# Adafruit_Feather_328P.net
KiCad netlist of a schematic drawn in EAGLE
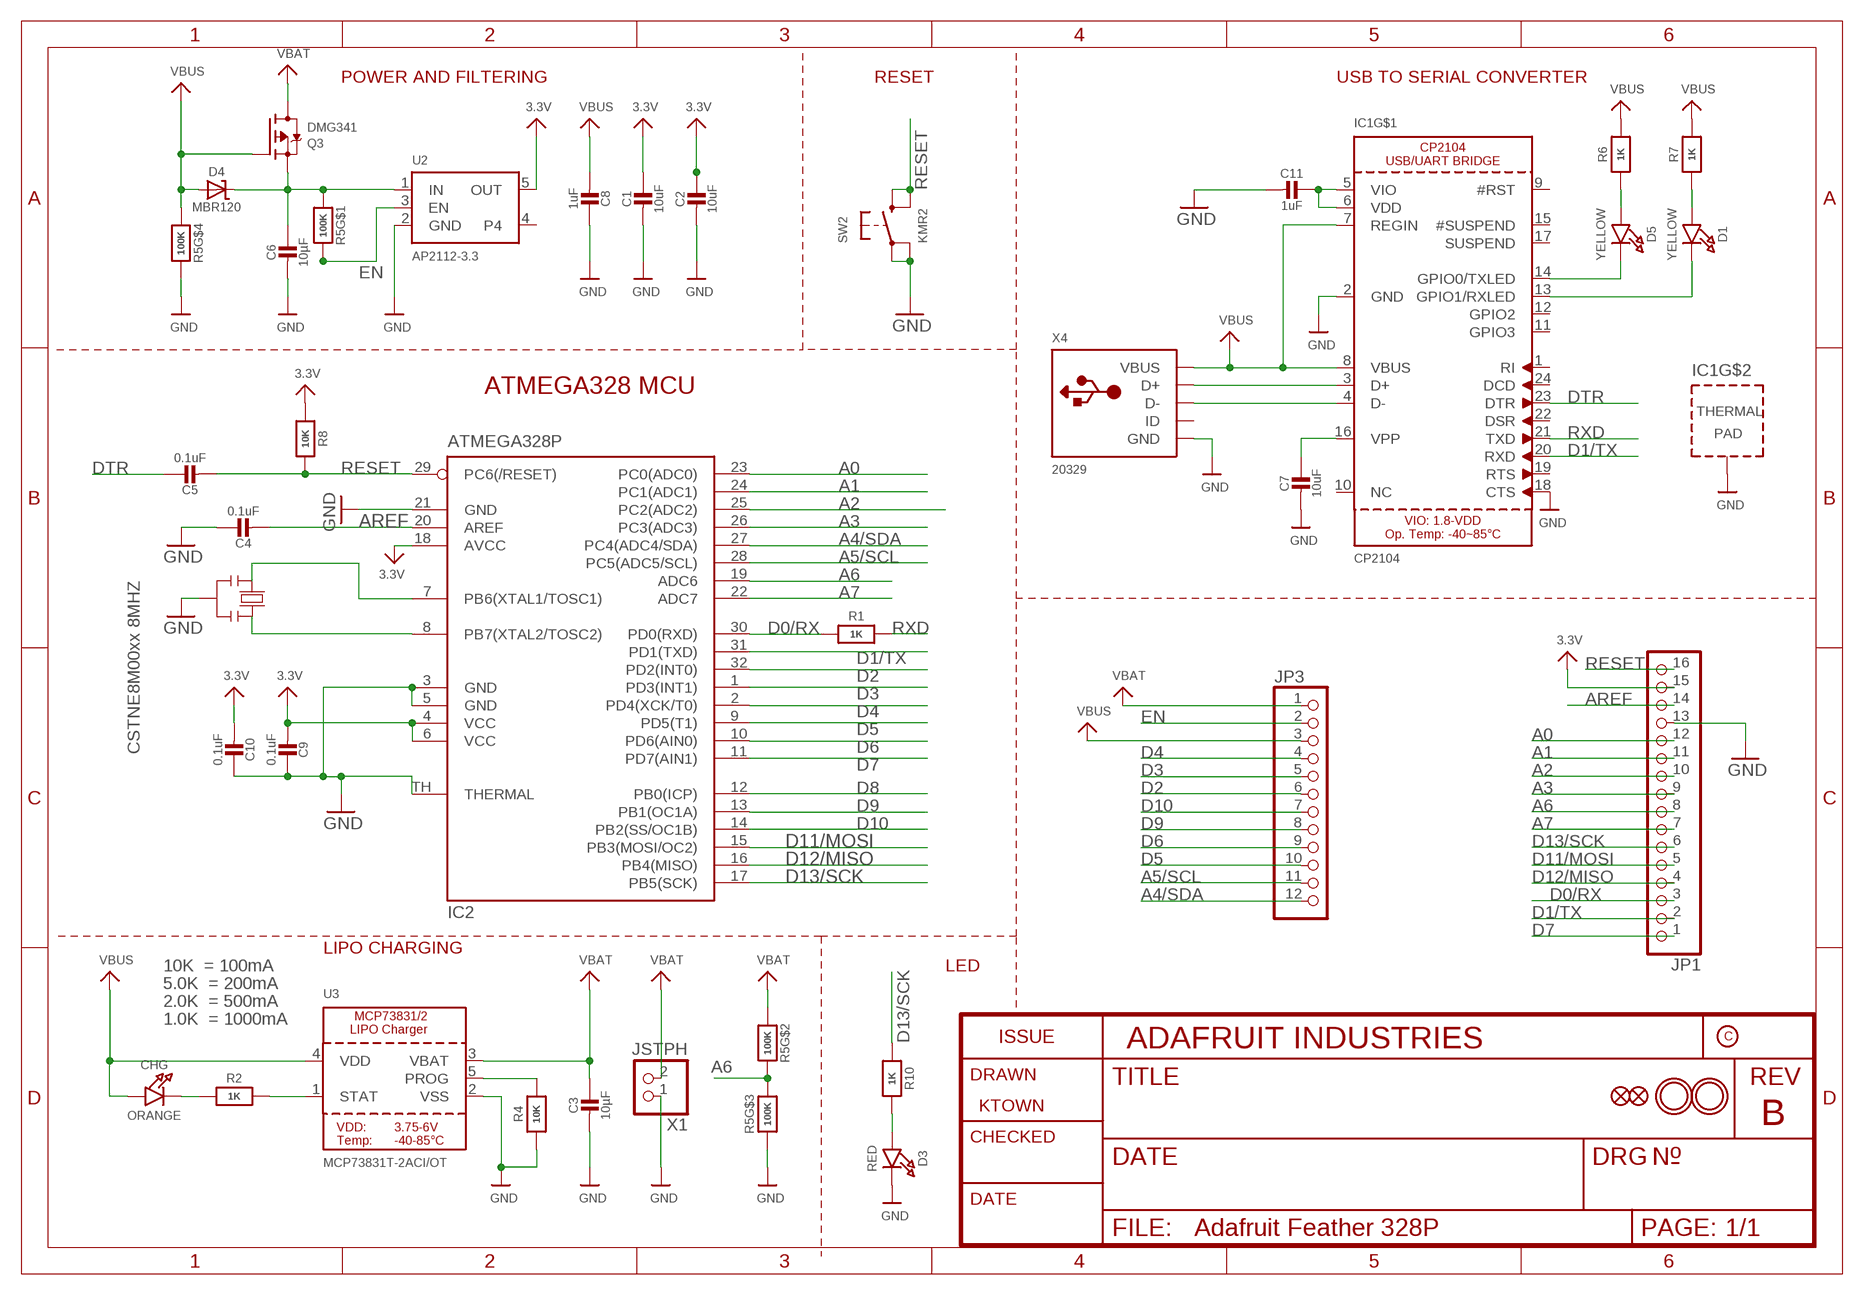
[diagram p0: schematic, sheet 1]

(export (version "E")
  (design (tool "Eeschema 10.0.6"))
  (components
    (comp (ref "C1")
      (value "10uF")
      (footprint "eagle-import:0805-NO")
      (libsource (lib "eagle-import") (part "CAP_CERAMIC0805-NOOUTLINE"))
    )
    (comp (ref "C2")
      (value "10uF")
      (footprint "eagle-import:0805-NO")
      (libsource (lib "eagle-import") (part "CAP_CERAMIC0805-NOOUTLINE"))
    )
    (comp (ref "C3")
      (value "10µF")
      (footprint "eagle-import:0805-NO")
      (libsource (lib "eagle-import") (part "CAP_CERAMIC0805-NOOUTLINE"))
    )
    (comp (ref "C4")
      (value "0.1uF")
      (footprint "eagle-import:0603-NO")
      (libsource (lib "eagle-import") (part "CAP_CERAMIC0603_NO"))
    )
    (comp (ref "C5")
      (value "0.1uF")
      (footprint "eagle-import:0603-NO")
      (libsource (lib "eagle-import") (part "CAP_CERAMIC0603_NO"))
    )
    (comp (ref "C6")
      (value "10µF")
      (footprint "eagle-import:0805-NO")
      (libsource (lib "eagle-import") (part "CAP_CERAMIC0805-NOOUTLINE"))
    )
    (comp (ref "C7")
      (value "10uF")
      (footprint "eagle-import:_0805MP")
      (libsource (lib "eagle-import") (part "CAP_CERAMIC_0805MP"))
    )
    (comp (ref "C8")
      (value "1uF")
      (footprint "eagle-import:0603-NO")
      (libsource (lib "eagle-import") (part "CAP_CERAMIC0603_NO"))
    )
    (comp (ref "C9")
      (value "0.1uF")
      (footprint "eagle-import:0603-NO")
      (libsource (lib "eagle-import") (part "CAP_CERAMIC0603_NO"))
    )
    (comp (ref "C10")
      (value "0.1uF")
      (footprint "eagle-import:0603-NO")
      (libsource (lib "eagle-import") (part "CAP_CERAMIC0603_NO"))
    )
    (comp (ref "C11")
      (value "1uF")
      (footprint "eagle-import:0603-NO")
      (libsource (lib "eagle-import") (part "CAP_CERAMIC0603_NO"))
    )
    (comp (ref "CHG")
      (value "ORANGE")
      (footprint "eagle-import:CHIPLED_0805_NOOUTLINE")
      (libsource (lib "eagle-import") (part "LED0805_NOOUTLINE"))
    )
    (comp (ref "D1")
      (value "YELLOW")
      (footprint "eagle-import:CHIPLED_0805_NOOUTLINE")
      (libsource (lib "eagle-import") (part "LED0805_NOOUTLINE"))
    )
    (comp (ref "D3")
      (value "RED")
      (footprint "eagle-import:CHIPLED_0805_NOOUTLINE")
      (libsource (lib "eagle-import") (part "LED0805_NOOUTLINE"))
    )
    (comp (ref "D4")
      (value "MBR120")
      (footprint "eagle-import:SOD-123")
      (libsource (lib "eagle-import") (part "DIODE-SCHOTTKYSOD-123"))
    )
    (comp (ref "D5")
      (value "YELLOW")
      (footprint "eagle-import:CHIPLED_0805_NOOUTLINE")
      (libsource (lib "eagle-import") (part "LED0805_NOOUTLINE"))
    )
    (comp (ref "IC1")
      (value "CP2104")
      (footprint "eagle-import:QFN24_4MM_SMSC")
      (libsource (lib "eagle-import") (part "CP2104"))
    )
    (comp (ref "IC2")
      (value "ATMEGA328P")
      (footprint "eagle-import:MLF32-TH")
      (fields (field (name "MPN") "ATMEGA88PA-MU"))
      (libsource (lib "eagle-import") (part "MEGA8-MI"))
    )
    (comp (ref "JP1")
      (value "HEADER-1X16ROUND")
      (footprint "eagle-import:1X16_ROUND")
      (libsource (lib "eagle-import") (part "HEADER-1X16ROUND"))
    )
    (comp (ref "JP3")
      (value "HEADER-1X12")
      (footprint "eagle-import:1X12_ROUND")
      (libsource (lib "eagle-import") (part "HEADER-1X12"))
    )
    (comp (ref "Q3")
      (value "DMG341")
      (footprint "eagle-import:SOT23-R")
      (libsource (lib "eagle-import") (part "MOSFET-P"))
    )
    (comp (ref "R1")
      (value "1K")
      (footprint "eagle-import:_0603MP")
      (libsource (lib "eagle-import") (part "RESISTOR_0603MP"))
    )
    (comp (ref "R2")
      (value "1K")
      (footprint "eagle-import:0603-NO")
      (libsource (lib "eagle-import") (part "RESISTOR_0603_NOOUT"))
    )
    (comp (ref "R4")
      (value "10K")
      (footprint "eagle-import:0603-NO")
      (libsource (lib "eagle-import") (part "RESISTOR_0603_NOOUT"))
    )
    (comp (ref "R5")
      (value "100K")
      (footprint "eagle-import:RESPACK_4X0603")
      (libsource (lib "eagle-import") (part "RESISTOR_4PACK"))
    )
    (comp (ref "R6")
      (value "1K")
      (footprint "eagle-import:0603-NO")
      (libsource (lib "eagle-import") (part "RESISTOR_0603_NOOUT"))
    )
    (comp (ref "R7")
      (value "1K")
      (footprint "eagle-import:0603-NO")
      (libsource (lib "eagle-import") (part "RESISTOR_0603_NOOUT"))
    )
    (comp (ref "R8")
      (value "10K")
      (footprint "eagle-import:0603-NO")
      (libsource (lib "eagle-import") (part "RESISTOR_0603_NOOUT"))
    )
    (comp (ref "R10")
      (value "1K")
      (footprint "eagle-import:0603-NO")
      (libsource (lib "eagle-import") (part "RESISTOR_0603_NOOUT"))
    )
    (comp (ref "SW2")
      (value "KMR2")
      (footprint "eagle-import:BTN_KMR2_4.6X2.8")
      (libsource (lib "eagle-import") (part "SWITCH_TACT_SMT4.6X2.8"))
    )
    (comp (ref "U$31")
      (value "MOUNTINGHOLE2.5")
      (footprint "eagle-import:MOUNTINGHOLE_2.5_PLATED")
      (libsource (lib "eagle-import") (part "MOUNTINGHOLE2.5"))
    )
    (comp (ref "U$32")
      (value "MOUNTINGHOLE2.5")
      (footprint "eagle-import:MOUNTINGHOLE_2.5_PLATED")
      (libsource (lib "eagle-import") (part "MOUNTINGHOLE2.5"))
    )
    (comp (ref "U$34")
      (value "FIDUCIAL_1MM")
      (footprint "eagle-import:FIDUCIAL_1MM")
      (libsource (lib "eagle-import") (part "FIDUCIAL_1MM"))
    )
    (comp (ref "U$35")
      (value "FIDUCIAL_1MM")
      (footprint "eagle-import:FIDUCIAL_1MM")
      (libsource (lib "eagle-import") (part "FIDUCIAL_1MM"))
    )
    (comp (ref "U2")
      (value "AP2112-3.3")
      (footprint "eagle-import:SOT23-5")
      (libsource (lib "eagle-import") (part "VREG_SOT23-5"))
    )
    (comp (ref "U3")
      (value "MCP73831T-2ACI/OT")
      (footprint "eagle-import:SOT23-5")
      (libsource (lib "eagle-import") (part "MCP73831/2"))
    )
    (comp (ref "X1")
      (value "JSTPH")
      (footprint "eagle-import:JSTPH2")
      (libsource (lib "eagle-import") (part "CON_JST_PH_2PIN"))
    )
    (comp (ref "X4")
      (value "20329")
      (footprint "eagle-import:4UCONN_20329_V2")
      (libsource (lib "eagle-import") (part "USB_MICRO_20329_V2"))
    )
    (comp (ref "Y2")
      (value "CSTNE8M00xx 8MHZ")
      (footprint "eagle-import:RESONATOR")
      (libsource (lib "eagle-import") (part "RESONATORMU"))
    )
  )
  (nets
    (net (code "1") (name "/A0") (class "Default")
      (node (ref "IC2") (pin "23") (pinfunction "PC0(ADC0)_23") (pintype "bidirectional"))
      (node (ref "JP1") (pin "12") (pinfunction "12_12") (pintype "passive"))
    )
    (net (code "2") (name "/A1") (class "Default")
      (node (ref "IC2") (pin "24") (pinfunction "PC1(ADC1)_24") (pintype "bidirectional"))
      (node (ref "JP1") (pin "11") (pinfunction "11_11") (pintype "passive"))
    )
    (net (code "3") (name "/A2") (class "Default")
      (node (ref "IC2") (pin "25") (pinfunction "PC2(ADC2)_25") (pintype "bidirectional"))
      (node (ref "JP1") (pin "10") (pinfunction "10_10") (pintype "passive"))
    )
    (net (code "4") (name "/A3") (class "Default")
      (node (ref "IC2") (pin "26") (pinfunction "PC3(ADC3)_26") (pintype "bidirectional"))
      (node (ref "JP1") (pin "9") (pinfunction "9_9") (pintype "passive"))
    )
    (net (code "5") (name "/A4{slash}SDA") (class "Default")
      (node (ref "IC2") (pin "27") (pinfunction "PC4(ADC4/SDA)_27") (pintype "bidirectional"))
      (node (ref "JP3") (pin "12") (pinfunction "12_12") (pintype "passive"))
    )
    (net (code "6") (name "/A5{slash}SCL") (class "Default")
      (node (ref "IC2") (pin "28") (pinfunction "PC5(ADC5/SCL)_28") (pintype "bidirectional"))
      (node (ref "JP3") (pin "11") (pinfunction "11_11") (pintype "passive"))
    )
    (net (code "7") (name "/A6") (class "Default")
      (node (ref "IC2") (pin "19") (pinfunction "ADC6_19") (pintype "bidirectional"))
      (node (ref "JP1") (pin "8") (pinfunction "8_8") (pintype "passive"))
      (node (ref "R5") (pin "6") (pinfunction "2_6") (pintype "passive"))
      (node (ref "R5") (pin "7") (pinfunction "2_7") (pintype "passive"))
    )
    (net (code "8") (name "/A7") (class "Default")
      (node (ref "IC2") (pin "22") (pinfunction "ADC7_22") (pintype "bidirectional"))
      (node (ref "JP1") (pin "7") (pinfunction "7_7") (pintype "passive"))
    )
    (net (code "9") (name "/AREF") (class "Default")
      (node (ref "C4") (pin "2") (pinfunction "2_2") (pintype "passive"))
      (node (ref "IC2") (pin "20") (pinfunction "AREF_20") (pintype "passive"))
      (node (ref "JP1") (pin "14") (pinfunction "14_14") (pintype "passive"))
    )
    (net (code "10") (name "/D0{slash}RX") (class "Default")
      (node (ref "IC2") (pin "30") (pinfunction "PD0(RXD)_30") (pintype "bidirectional"))
      (node (ref "JP1") (pin "3") (pinfunction "3_3") (pintype "passive"))
      (node (ref "R1") (pin "1") (pinfunction "1_1") (pintype "passive"))
    )
    (net (code "11") (name "/D1{slash}TX") (class "Default")
      (node (ref "IC1") (pin "20") (pinfunction "RXD_20") (pintype "input"))
      (node (ref "IC2") (pin "31") (pinfunction "PD1(TXD)_31") (pintype "bidirectional"))
      (node (ref "JP1") (pin "2") (pinfunction "2_2") (pintype "passive"))
    )
    (net (code "12") (name "/D2") (class "Default")
      (node (ref "IC2") (pin "32") (pinfunction "PD2(INT0)_32") (pintype "bidirectional"))
      (node (ref "JP3") (pin "6") (pinfunction "6_6") (pintype "passive"))
    )
    (net (code "13") (name "/D3") (class "Default")
      (node (ref "IC2") (pin "1") (pinfunction "PD3(INT1)_1") (pintype "bidirectional"))
      (node (ref "JP3") (pin "5") (pinfunction "5_5") (pintype "passive"))
    )
    (net (code "14") (name "/D4") (class "Default")
      (node (ref "IC2") (pin "2") (pinfunction "PD4(XCK/T0)_2") (pintype "bidirectional"))
      (node (ref "JP3") (pin "4") (pinfunction "4_4") (pintype "passive"))
    )
    (net (code "15") (name "/D5") (class "Default")
      (node (ref "IC2") (pin "9") (pinfunction "PD5(T1)_9") (pintype "bidirectional"))
      (node (ref "JP3") (pin "10") (pinfunction "10_10") (pintype "passive"))
    )
    (net (code "16") (name "/D6") (class "Default")
      (node (ref "IC2") (pin "10") (pinfunction "PD6(AIN0)_10") (pintype "bidirectional"))
      (node (ref "JP3") (pin "9") (pinfunction "9_9") (pintype "passive"))
    )
    (net (code "17") (name "/D7") (class "Default")
      (node (ref "IC2") (pin "11") (pinfunction "PD7(AIN1)_11") (pintype "bidirectional"))
      (node (ref "JP1") (pin "1") (pinfunction "1_1") (pintype "passive"))
    )
    (net (code "18") (name "/D8") (class "Default")
      (node (ref "IC2") (pin "12") (pinfunction "PB0(ICP)_12") (pintype "bidirectional"))
    )
    (net (code "19") (name "/D9") (class "Default")
      (node (ref "IC2") (pin "13") (pinfunction "PB1(OC1A)_13") (pintype "bidirectional"))
      (node (ref "JP3") (pin "8") (pinfunction "8_8") (pintype "passive"))
    )
    (net (code "20") (name "/D10") (class "Default")
      (node (ref "IC2") (pin "14") (pinfunction "PB2(SS/OC1B)_14") (pintype "bidirectional"))
      (node (ref "JP3") (pin "7") (pinfunction "7_7") (pintype "passive"))
    )
    (net (code "21") (name "/D11{slash}MOSI") (class "Default")
      (node (ref "IC2") (pin "15") (pinfunction "PB3(MOSI/OC2)_15") (pintype "bidirectional"))
      (node (ref "JP1") (pin "5") (pinfunction "5_5") (pintype "passive"))
    )
    (net (code "22") (name "/D12{slash}MISO") (class "Default")
      (node (ref "IC2") (pin "16") (pinfunction "PB4(MISO)_16") (pintype "bidirectional"))
      (node (ref "JP1") (pin "4") (pinfunction "4_4") (pintype "passive"))
    )
    (net (code "23") (name "/D13{slash}SCK") (class "Default")
      (node (ref "IC2") (pin "17") (pinfunction "PB5(SCK)_17") (pintype "bidirectional"))
      (node (ref "JP1") (pin "6") (pinfunction "6_6") (pintype "passive"))
      (node (ref "R10") (pin "1") (pinfunction "1_1") (pintype "passive"))
    )
    (net (code "24") (name "/DTR") (class "Default")
      (node (ref "C5") (pin "1") (pinfunction "1_1") (pintype "passive"))
      (node (ref "IC1") (pin "23") (pinfunction "DTR_23") (pintype "output"))
    )
    (net (code "25") (name "/EN") (class "Default")
      (node (ref "JP3") (pin "2") (pinfunction "2_2") (pintype "passive"))
      (node (ref "R5") (pin "8") (pinfunction "2_8") (pintype "passive"))
      (node (ref "U2") (pin "3") (pinfunction "EN_3") (pintype "input"))
    )
    (net (code "26") (name "/RESET") (class "Default")
      (node (ref "C5") (pin "2") (pinfunction "2_2") (pintype "passive"))
      (node (ref "IC2") (pin "29") (pinfunction "PC6(/RESET)_29") (pintype "bidirectional"))
      (node (ref "JP1") (pin "16") (pinfunction "16_16") (pintype "passive"))
      (node (ref "R8") (pin "1") (pinfunction "1_1") (pintype "passive"))
      (node (ref "SW2") (pin "B") (pinfunction "S_B") (pintype "passive"))
      (node (ref "SW2") (pin "B'") (pinfunction "S1_B'") (pintype "passive"))
    )
    (net (code "27") (name "/RXD") (class "Default")
      (node (ref "IC1") (pin "21") (pinfunction "TXD_21") (pintype "output"))
      (node (ref "R1") (pin "2") (pinfunction "2_2") (pintype "passive"))
    )
    (net (code "28") (name "3.3V") (class "Default")
      (node (ref "C1") (pin "1") (pinfunction "1_1") (pintype "passive"))
      (node (ref "C10") (pin "2") (pinfunction "2_2") (pintype "passive"))
      (node (ref "C2") (pin "1") (pinfunction "1_1") (pintype "passive"))
      (node (ref "C9") (pin "2") (pinfunction "2_2") (pintype "passive"))
      (node (ref "IC2") (pin "18") (pinfunction "AVCC_18") (pintype "power_in"))
      (node (ref "IC2") (pin "4") (pinfunction "VCC_4") (pintype "power_in"))
      (node (ref "IC2") (pin "6") (pinfunction "VCC_6") (pintype "power_in"))
      (node (ref "JP1") (pin "15") (pinfunction "15_15") (pintype "passive"))
      (node (ref "R8") (pin "2") (pinfunction "2_2") (pintype "passive"))
      (node (ref "U2") (pin "5") (pinfunction "OUT_5") (pintype "power_in"))
    )
    (net (code "29") (name "GND") (class "Default")
      (node (ref "C1") (pin "2") (pinfunction "2_2") (pintype "passive"))
      (node (ref "C10") (pin "1") (pinfunction "1_1") (pintype "passive"))
      (node (ref "C11") (pin "2") (pinfunction "2_2") (pintype "passive"))
      (node (ref "C2") (pin "2") (pinfunction "2_2") (pintype "passive"))
      (node (ref "C3") (pin "2") (pinfunction "2_2") (pintype "passive"))
      (node (ref "C4") (pin "1") (pinfunction "1_1") (pintype "passive"))
      (node (ref "C6") (pin "2") (pinfunction "2_2") (pintype "passive"))
      (node (ref "C7") (pin "2") (pinfunction "2_2") (pintype "passive"))
      (node (ref "C8") (pin "1") (pinfunction "1_1") (pintype "passive"))
      (node (ref "C9") (pin "1") (pinfunction "1_1") (pintype "passive"))
      (node (ref "D3") (pin "C") (pinfunction "C_C") (pintype "passive"))
      (node (ref "IC1") (pin "18") (pinfunction "CTS_18") (pintype "input"))
      (node (ref "IC1") (pin "2") (pinfunction "GND_2") (pintype "power_in"))
      (node (ref "IC1") (pin "THERM") (pinfunction "TP_THERM") (pintype "power_in"))
      (node (ref "IC2") (pin "21") (pinfunction "GND_21") (pintype "power_in"))
      (node (ref "IC2") (pin "3") (pinfunction "GND_3") (pintype "power_in"))
      (node (ref "IC2") (pin "5") (pinfunction "GND_5") (pintype "power_in"))
      (node (ref "IC2") (pin "TH") (pinfunction "THERMAL_TH") (pintype "passive"))
      (node (ref "JP1") (pin "13") (pinfunction "13_13") (pintype "passive"))
      (node (ref "R4") (pin "1") (pinfunction "1_1") (pintype "passive"))
      (node (ref "R5") (pin "3") (pinfunction "1_3") (pintype "passive"))
      (node (ref "R5") (pin "5") (pinfunction "2_5") (pintype "passive"))
      (node (ref "SW2") (pin "A") (pinfunction "P_A") (pintype "passive"))
      (node (ref "SW2") (pin "A'") (pinfunction "P1_A'") (pintype "passive"))
      (node (ref "U2") (pin "2") (pinfunction "GND_2") (pintype "power_in"))
      (node (ref "U3") (pin "2") (pinfunction "VSS_2") (pintype "power_in"))
      (node (ref "X1") (pin "1") (pinfunction "1_1") (pintype "passive"))
      (node (ref "X4") (pin "BASE@1") (pinfunction "GND_BASE@1") (pintype "power_in"))
      (node (ref "X4") (pin "BASE@2") (pinfunction "GND_BASE@2") (pintype "power_in"))
      (node (ref "X4") (pin "GND") (pinfunction "GND_GND") (pintype "power_in"))
      (node (ref "X4") (pin "SPRT@1") (pinfunction "GND_SPRT@1") (pintype "power_in"))
      (node (ref "X4") (pin "SPRT@2") (pinfunction "GND_SPRT@2") (pintype "power_in"))
      (node (ref "X4") (pin "SPRT@3") (pinfunction "GND_SPRT@3") (pintype "power_in"))
      (node (ref "X4") (pin "SPRT@4") (pinfunction "GND_SPRT@4") (pintype "power_in"))
      (node (ref "Y2") (pin "2") (pinfunction "2_2") (pintype "passive"))
    )
    (net (code "30") (name "Net-(CHG-PadC)") (class "Default")
      (node (ref "CHG") (pin "C") (pinfunction "C_C") (pintype "passive"))
      (node (ref "R2") (pin "1") (pinfunction "1_1") (pintype "passive"))
    )
    (net (code "31") (name "Net-(D1-PadA)") (class "Default")
      (node (ref "D1") (pin "A") (pinfunction "A_A") (pintype "passive"))
      (node (ref "R7") (pin "1") (pinfunction "1_1") (pintype "passive"))
    )
    (net (code "32") (name "Net-(D3-PadA)") (class "Default")
      (node (ref "D3") (pin "A") (pinfunction "A_A") (pintype "passive"))
      (node (ref "R10") (pin "2") (pinfunction "2_2") (pintype "passive"))
    )
    (net (code "33") (name "Net-(D5-PadA)") (class "Default")
      (node (ref "D5") (pin "A") (pinfunction "A_A") (pintype "passive"))
      (node (ref "R6") (pin "1") (pinfunction "1_1") (pintype "passive"))
    )
    (net (code "34") (name "Net-(IC1A-D+)") (class "Default")
      (node (ref "IC1") (pin "3") (pinfunction "D+_3") (pintype "bidirectional"))
      (node (ref "X4") (pin "D+") (pinfunction "D+_D+") (pintype "bidirectional"))
    )
    (net (code "35") (name "Net-(IC1A-D-)") (class "Default")
      (node (ref "IC1") (pin "4") (pinfunction "D-_4") (pintype "bidirectional"))
      (node (ref "X4") (pin "D-") (pinfunction "D-_D-") (pintype "bidirectional"))
    )
    (net (code "36") (name "Net-(IC1A-GPIO0{slash}TXLED)") (class "Default")
      (node (ref "D5") (pin "C") (pinfunction "C_C") (pintype "passive"))
      (node (ref "IC1") (pin "14") (pinfunction "GPIO0/TXLED_14") (pintype "bidirectional"))
    )
    (net (code "37") (name "Net-(IC1A-GPIO1{slash}RXLED)") (class "Default")
      (node (ref "D1") (pin "C") (pinfunction "C_C") (pintype "passive"))
      (node (ref "IC1") (pin "13") (pinfunction "GPIO1/RXLED_13") (pintype "bidirectional"))
    )
    (net (code "38") (name "Net-(IC1A-VDD)") (class "Default")
      (node (ref "C11") (pin "1") (pinfunction "1_1") (pintype "passive"))
      (node (ref "IC1") (pin "5") (pinfunction "VIO_5") (pintype "power_in"))
      (node (ref "IC1") (pin "6") (pinfunction "VDD_6") (pintype "power_in"))
    )
    (net (code "39") (name "Net-(IC1A-VPP)") (class "Default")
      (node (ref "C7") (pin "1") (pinfunction "1_1") (pintype "passive"))
      (node (ref "IC1") (pin "16") (pinfunction "VPP_16") (pintype "bidirectional"))
    )
    (net (code "40") (name "Net-(IC2-PB6(XTAL1{slash}TOSC1))") (class "Default")
      (node (ref "IC2") (pin "7") (pinfunction "PB6(XTAL1/TOSC1)_7") (pintype "bidirectional"))
      (node (ref "Y2") (pin "1") (pinfunction "1_1") (pintype "passive"))
    )
    (net (code "41") (name "Net-(IC2-PB7(XTAL2{slash}TOSC2))") (class "Default")
      (node (ref "IC2") (pin "8") (pinfunction "PB7(XTAL2/TOSC2)_8") (pintype "bidirectional"))
      (node (ref "Y2") (pin "3") (pinfunction "3_3") (pintype "passive"))
    )
    (net (code "42") (name "Net-(Q3-S)") (class "Default")
      (node (ref "C6") (pin "1") (pinfunction "1_1") (pintype "passive"))
      (node (ref "D4") (pin "C") (pinfunction "C_C") (pintype "passive"))
      (node (ref "Q3") (pin "2") (pinfunction "S_2") (pintype "passive"))
      (node (ref "R5") (pin "1") (pinfunction "1_1") (pintype "passive"))
      (node (ref "U2") (pin "1") (pinfunction "IN_1") (pintype "power_in"))
    )
    (net (code "43") (name "Net-(U3-PROG)") (class "Default")
      (node (ref "R4") (pin "2") (pinfunction "2_2") (pintype "passive"))
      (node (ref "U3") (pin "5") (pinfunction "PROG_5") (pintype "input"))
    )
    (net (code "44") (name "Net-(U3-STAT)") (class "Default")
      (node (ref "R2") (pin "2") (pinfunction "2_2") (pintype "passive"))
      (node (ref "U3") (pin "1") (pinfunction "STAT_1") (pintype "output"))
    )
    (net (code "45") (name "VBAT") (class "Default")
      (node (ref "C3") (pin "1") (pinfunction "1_1") (pintype "passive"))
      (node (ref "JP3") (pin "1") (pinfunction "1_1") (pintype "passive"))
      (node (ref "Q3") (pin "3") (pinfunction "D_3") (pintype "passive"))
      (node (ref "R5") (pin "2") (pinfunction "1_2") (pintype "passive"))
      (node (ref "U3") (pin "3") (pinfunction "VBAT_3") (pintype "power_in"))
      (node (ref "X1") (pin "2") (pinfunction "2_2") (pintype "passive"))
    )
    (net (code "46") (name "VBUS") (class "Default")
      (node (ref "C8") (pin "2") (pinfunction "2_2") (pintype "passive"))
      (node (ref "CHG") (pin "A") (pinfunction "A_A") (pintype "passive"))
      (node (ref "D4") (pin "A") (pinfunction "A_A") (pintype "passive"))
      (node (ref "IC1") (pin "7") (pinfunction "REGIN_7") (pintype "power_in"))
      (node (ref "IC1") (pin "8") (pinfunction "VBUS_8") (pintype "power_in"))
      (node (ref "JP3") (pin "3") (pinfunction "3_3") (pintype "passive"))
      (node (ref "Q3") (pin "1") (pinfunction "G_1") (pintype "passive"))
      (node (ref "R5") (pin "4") (pinfunction "1_4") (pintype "passive"))
      (node (ref "R6") (pin "2") (pinfunction "2_2") (pintype "passive"))
      (node (ref "R7") (pin "2") (pinfunction "2_2") (pintype "passive"))
      (node (ref "U3") (pin "4") (pinfunction "VDD_4") (pintype "power_in"))
      (node (ref "X4") (pin "VBUS") (pinfunction "VBUS_VBUS") (pintype "power_in"))
    )
    (net (code "47") (name "unconnected-(IC1A-#RST-Pad9)") (class "Default")
      (node (ref "IC1") (pin "9") (pinfunction "#RST_9") (pintype "bidirectional"))
    )
    (net (code "48") (name "unconnected-(IC1A-#SUSPEND-Pad15)") (class "Default")
      (node (ref "IC1") (pin "15") (pinfunction "#SUSPEND_15") (pintype "output"))
    )
    (net (code "49") (name "unconnected-(IC1A-DCD-Pad24)") (class "Default")
      (node (ref "IC1") (pin "24") (pinfunction "DCD_24") (pintype "input"))
    )
    (net (code "50") (name "unconnected-(IC1A-DSR-Pad22)") (class "Default")
      (node (ref "IC1") (pin "22") (pinfunction "DSR_22") (pintype "input"))
    )
    (net (code "51") (name "unconnected-(IC1A-GPIO2-Pad12)") (class "Default")
      (node (ref "IC1") (pin "12") (pinfunction "GPIO2_12") (pintype "bidirectional"))
    )
    (net (code "52") (name "unconnected-(IC1A-GPIO3-Pad11)") (class "Default")
      (node (ref "IC1") (pin "11") (pinfunction "GPIO3_11") (pintype "bidirectional"))
    )
    (net (code "53") (name "unconnected-(IC1A-NC-Pad10)") (class "Default")
      (node (ref "IC1") (pin "10") (pinfunction "NC_10") (pintype "no_connect"))
    )
    (net (code "54") (name "unconnected-(IC1A-RI-Pad1)") (class "Default")
      (node (ref "IC1") (pin "1") (pinfunction "RI_1") (pintype "input"))
    )
    (net (code "55") (name "unconnected-(IC1A-RTS-Pad19)") (class "Default")
      (node (ref "IC1") (pin "19") (pinfunction "RTS_19") (pintype "output"))
    )
    (net (code "56") (name "unconnected-(IC1A-SUSPEND-Pad17)") (class "Default")
      (node (ref "IC1") (pin "17") (pinfunction "SUSPEND_17") (pintype "output"))
    )
    (net (code "57") (name "unconnected-(U2-P4-Pad4)") (class "Default")
      (node (ref "U2") (pin "4") (pinfunction "P4_4") (pintype "bidirectional"))
    )
    (net (code "58") (name "unconnected-(X4-PadID)") (class "Default")
      (node (ref "X4") (pin "ID") (pinfunction "ID_ID") (pintype "bidirectional"))
    )
  )
)
